# RPi-UNO-HAT_v10.net
KiCad netlist of a schematic drawn in EAGLE
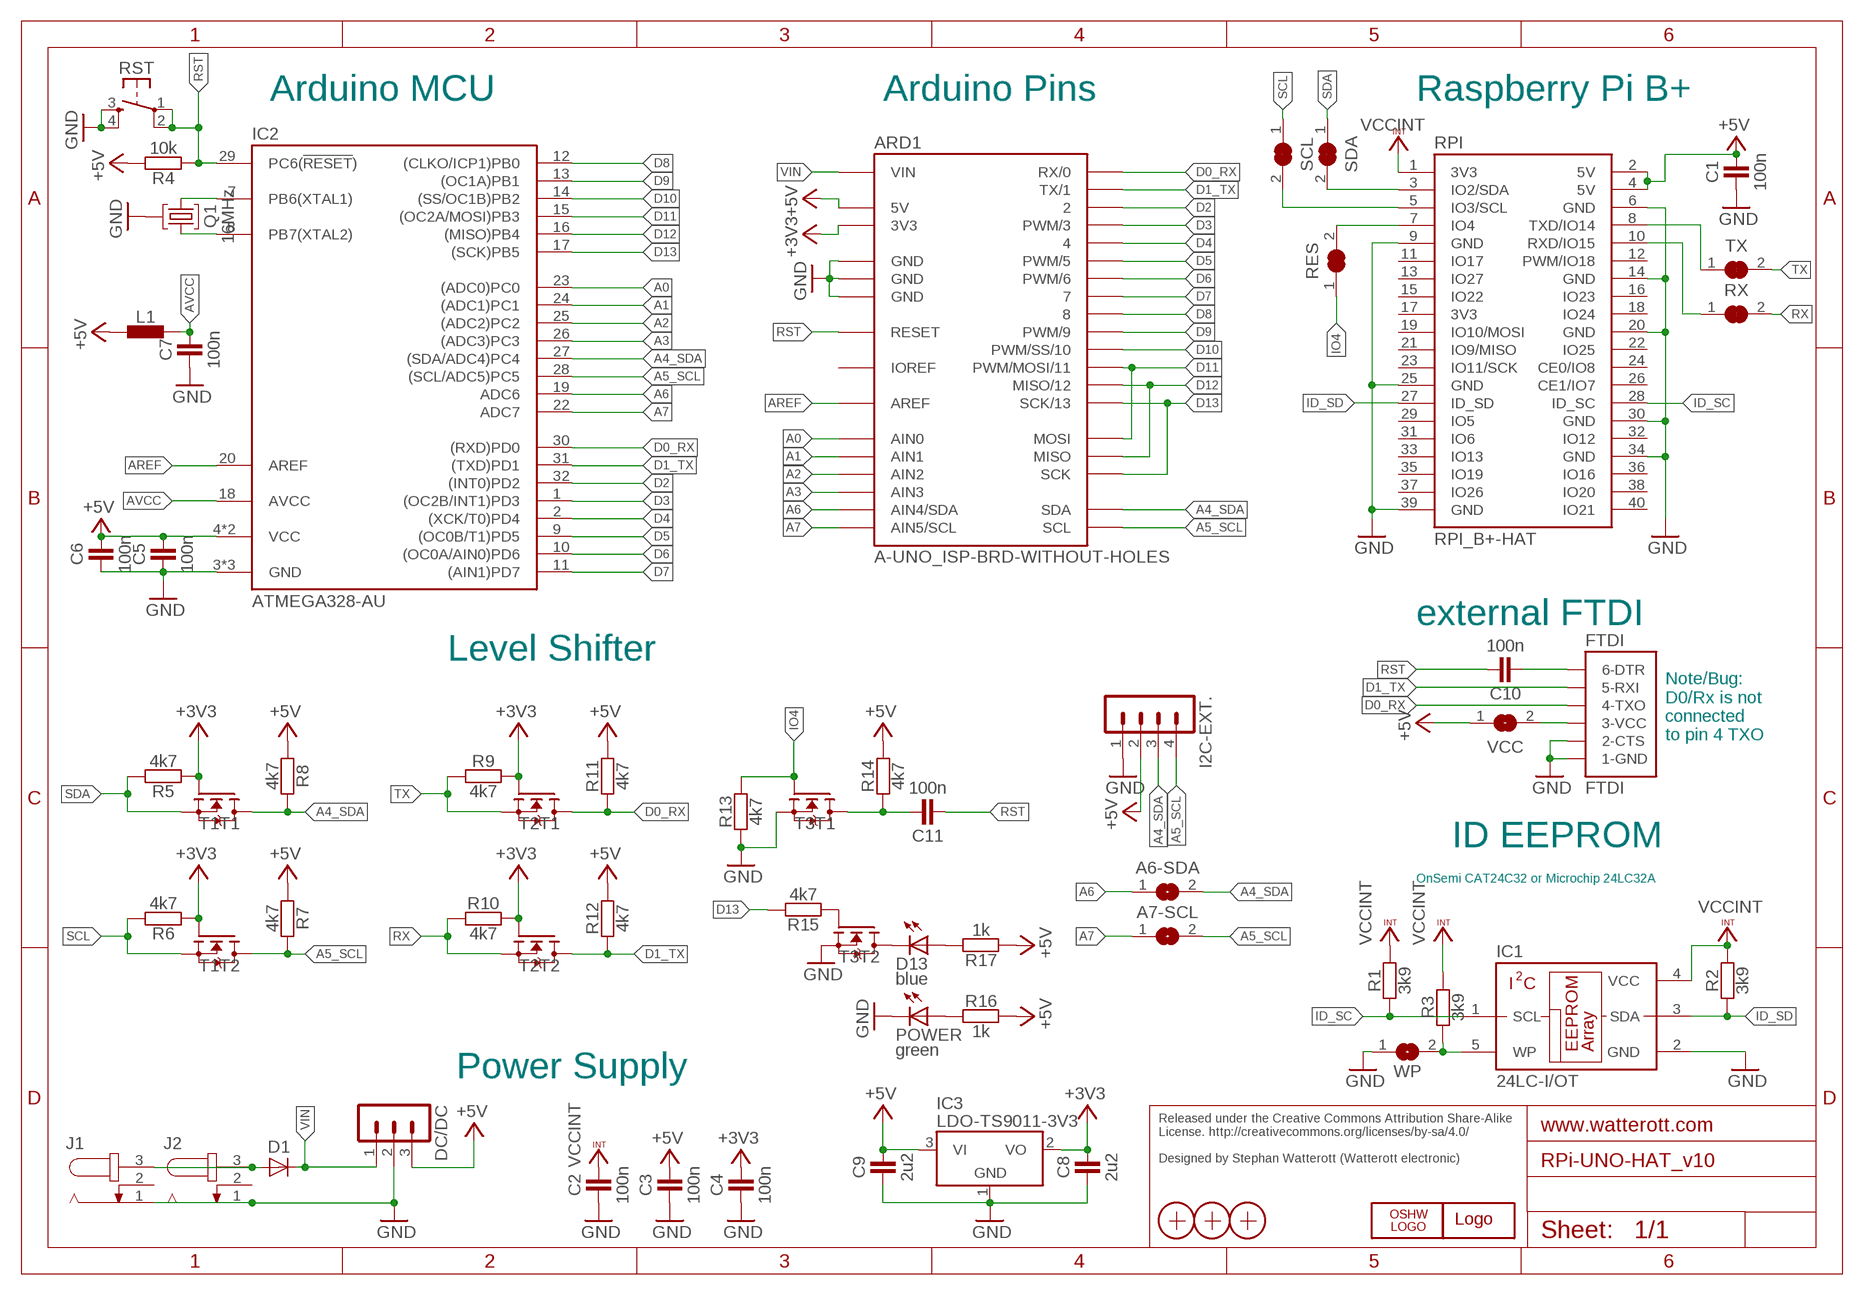
[diagram p0: schematic, sheet 1]

(export (version "E")
  (design (tool "Eeschema 10.0.6"))
  (components
    (comp (ref "A6-SDA")
      (value "JUMPER2-0402-NC")
      (footprint "eagle-import:JUMPER2-0402_NC")
      (libsource (lib "eagle-import") (part "JUMPER2-0402-NC"))
    )
    (comp (ref "A7-SCL")
      (value "JUMPER2-0402-NC")
      (footprint "eagle-import:JUMPER2-0402_NC")
      (libsource (lib "eagle-import") (part "JUMPER2-0402-NC"))
    )
    (comp (ref "ARD1")
      (value "A-UNO_ISP-BRD-WITHOUT-HOLES")
      (footprint "eagle-import:A-UNO-ISP_CON-WITHOUT-HOLES")
      (libsource (lib "eagle-import") (part "A-UNO_ISP-BRD-WITHOUT-HOLES"))
    )
    (comp (ref "C1")
      (value "100n")
      (footprint "eagle-import:C0402")
      (libsource (lib "eagle-import") (part "CAPACITOR-0402"))
    )
    (comp (ref "C2")
      (value "100n")
      (footprint "eagle-import:C0402")
      (libsource (lib "eagle-import") (part "CAPACITOR-0402"))
    )
    (comp (ref "C3")
      (value "100n")
      (footprint "eagle-import:C0402")
      (libsource (lib "eagle-import") (part "CAPACITOR-0402"))
    )
    (comp (ref "C4")
      (value "100n")
      (footprint "eagle-import:C0402")
      (libsource (lib "eagle-import") (part "CAPACITOR-0402"))
    )
    (comp (ref "C5")
      (value "100n")
      (footprint "eagle-import:C0402")
      (libsource (lib "eagle-import") (part "CAPACITOR-0402"))
    )
    (comp (ref "C6")
      (value "100n")
      (footprint "eagle-import:C0402")
      (libsource (lib "eagle-import") (part "CAPACITOR-0402"))
    )
    (comp (ref "C7")
      (value "100n")
      (footprint "eagle-import:C0402")
      (libsource (lib "eagle-import") (part "CAPACITOR-0402"))
    )
    (comp (ref "C8")
      (value "2u2")
      (footprint "eagle-import:C0402")
      (libsource (lib "eagle-import") (part "CAPACITOR-0402"))
    )
    (comp (ref "C9")
      (value "2u2")
      (footprint "eagle-import:C0402")
      (libsource (lib "eagle-import") (part "CAPACITOR-0402"))
    )
    (comp (ref "C10")
      (value "100n")
      (footprint "eagle-import:C0402")
      (libsource (lib "eagle-import") (part "CAPACITOR-0402"))
    )
    (comp (ref "C11")
      (value "100n")
      (footprint "eagle-import:C0402")
      (libsource (lib "eagle-import") (part "CAPACITOR-0402"))
    )
    (comp (ref "D1")
      (value "DIODE-SOD80")
      (footprint "eagle-import:SOD80")
      (libsource (lib "eagle-import") (part "DIODE-SOD80"))
    )
    (comp (ref "D13")
      (value "blue")
      (footprint "eagle-import:C0603")
      (libsource (lib "eagle-import") (part "LED-0603"))
    )
    (comp (ref "DC/DC")
      (value "MA03-1")
      (footprint "eagle-import:MA03-1")
      (libsource (lib "eagle-import") (part "MA03-1"))
    )
    (comp (ref "FTDI")
      (value "FTDI")
      (footprint "eagle-import:FTDI")
      (libsource (lib "eagle-import") (part "FTDI"))
    )
    (comp (ref "I2C-EXT.")
      (value "JST_PH_4B4B-PH-SM4-TB")
      (footprint "eagle-import:JST_B4B-PH-SM4-TB")
      (libsource (lib "eagle-import") (part "JST_PH_4B4B-PH-SM4-TB"))
    )
    (comp (ref "IC1")
      (value "24LC-I/OT")
      (footprint "eagle-import:SOT23-5")
      (libsource (lib "eagle-import") (part "24LC-I/OT"))
    )
    (comp (ref "IC2")
      (value "ATMEGA328-AU")
      (footprint "eagle-import:TQFP32")
      (libsource (lib "eagle-import") (part "ATMEGA328-AU"))
    )
    (comp (ref "IC3")
      (value "LDO-TS9011-3V3")
      (footprint "eagle-import:SOT23")
      (libsource (lib "eagle-import") (part "LDO-TS9011-3V3"))
    )
    (comp (ref "J1")
      (value "DC-JACK")
      (footprint "eagle-import:DC-JACK")
      (libsource (lib "eagle-import") (part "DC-JACK"))
    )
    (comp (ref "J2")
      (value "DC-JACK")
      (footprint "eagle-import:DC-JACK")
      (libsource (lib "eagle-import") (part "DC-JACK"))
    )
    (comp (ref "L1")
      (value "INDUCTOR-0603")
      (footprint "eagle-import:C0603")
      (libsource (lib "eagle-import") (part "INDUCTOR-0603"))
    )
    (comp (ref "LOGO1")
      (value "LOGO-S_PLACE_S")
      (footprint "eagle-import:SPARK_TPLACE_S")
      (libsource (lib "eagle-import") (part "LOGO-S_PLACE_S"))
    )
    (comp (ref "LOGO2")
      (value "OSHW_LOGOX0070")
      (footprint "eagle-import:OSHW_6X70")
      (libsource (lib "eagle-import") (part "OSHW_LOGOX0070"))
    )
    (comp (ref "POWER")
      (value "green")
      (footprint "eagle-import:C0603")
      (libsource (lib "eagle-import") (part "LED-0603"))
    )
    (comp (ref "Q1")
      (value "16MHz")
      (footprint "eagle-import:CRYSTAL_32X13")
      (libsource (lib "eagle-import") (part "CRYSTAL-RES-32"))
    )
    (comp (ref "R1")
      (value "3k9")
      (footprint "eagle-import:C0402")
      (libsource (lib "eagle-import") (part "RESISTOR-0402"))
    )
    (comp (ref "R2")
      (value "3k9")
      (footprint "eagle-import:C0402")
      (libsource (lib "eagle-import") (part "RESISTOR-0402"))
    )
    (comp (ref "R3")
      (value "3k9")
      (footprint "eagle-import:C0402")
      (libsource (lib "eagle-import") (part "RESISTOR-0402"))
    )
    (comp (ref "R4")
      (value "10k")
      (footprint "eagle-import:C0402")
      (libsource (lib "eagle-import") (part "RESISTOR-0402"))
    )
    (comp (ref "R5")
      (value "4k7")
      (footprint "eagle-import:C0402")
      (libsource (lib "eagle-import") (part "RESISTOR-0402"))
    )
    (comp (ref "R6")
      (value "4k7")
      (footprint "eagle-import:C0402")
      (libsource (lib "eagle-import") (part "RESISTOR-0402"))
    )
    (comp (ref "R7")
      (value "4k7")
      (footprint "eagle-import:C0402")
      (libsource (lib "eagle-import") (part "RESISTOR-0402"))
    )
    (comp (ref "R8")
      (value "4k7")
      (footprint "eagle-import:C0402")
      (libsource (lib "eagle-import") (part "RESISTOR-0402"))
    )
    (comp (ref "R9")
      (value "4k7")
      (footprint "eagle-import:C0402")
      (libsource (lib "eagle-import") (part "RESISTOR-0402"))
    )
    (comp (ref "R10")
      (value "4k7")
      (footprint "eagle-import:C0402")
      (libsource (lib "eagle-import") (part "RESISTOR-0402"))
    )
    (comp (ref "R11")
      (value "4k7")
      (footprint "eagle-import:C0402")
      (libsource (lib "eagle-import") (part "RESISTOR-0402"))
    )
    (comp (ref "R12")
      (value "4k7")
      (footprint "eagle-import:C0402")
      (libsource (lib "eagle-import") (part "RESISTOR-0402"))
    )
    (comp (ref "R13")
      (value "4k7")
      (footprint "eagle-import:C0402")
      (libsource (lib "eagle-import") (part "RESISTOR-0402"))
    )
    (comp (ref "R14")
      (value "4k7")
      (footprint "eagle-import:C0402")
      (libsource (lib "eagle-import") (part "RESISTOR-0402"))
    )
    (comp (ref "R15")
      (value "4k7")
      (footprint "eagle-import:C0402")
      (libsource (lib "eagle-import") (part "RESISTOR-0402"))
    )
    (comp (ref "R16")
      (value "1k")
      (footprint "eagle-import:C0402")
      (libsource (lib "eagle-import") (part "RESISTOR-0402"))
    )
    (comp (ref "R17")
      (value "1k")
      (footprint "eagle-import:C0402")
      (libsource (lib "eagle-import") (part "RESISTOR-0402"))
    )
    (comp (ref "RES")
      (value "JUMPER2-0402-NC")
      (footprint "eagle-import:JUMPER2-0402_NC")
      (libsource (lib "eagle-import") (part "JUMPER2-0402-NC"))
    )
    (comp (ref "RPI")
      (value "RPI_B+-HAT")
      (footprint "eagle-import:RPI-B+HAT")
      (libsource (lib "eagle-import") (part "RPI_B+-HAT"))
    )
    (comp (ref "RST")
      (value "SW-TACTILE-PTS840P")
      (footprint "eagle-import:SW_PTS840P")
      (libsource (lib "eagle-import") (part "SW-TACTILE-PTS840P"))
    )
    (comp (ref "RX")
      (value "JUMPER2-0402-NC")
      (footprint "eagle-import:JUMPER2-0402_NC")
      (libsource (lib "eagle-import") (part "JUMPER2-0402-NC"))
    )
    (comp (ref "SCL")
      (value "JUMPER2-0402-NC")
      (footprint "eagle-import:JUMPER2-0402_NC")
      (libsource (lib "eagle-import") (part "JUMPER2-0402-NC"))
    )
    (comp (ref "SDA")
      (value "JUMPER2-0402-NC")
      (footprint "eagle-import:JUMPER2-0402_NC")
      (libsource (lib "eagle-import") (part "JUMPER2-0402-NC"))
    )
    (comp (ref "T1")
      (value "BSS138PS")
      (footprint "eagle-import:SOT363")
      (libsource (lib "eagle-import") (part "BSS138PS"))
    )
    (comp (ref "T2")
      (value "BSS138PS")
      (footprint "eagle-import:SOT363")
      (libsource (lib "eagle-import") (part "BSS138PS"))
    )
    (comp (ref "T3")
      (value "BSS138PS")
      (footprint "eagle-import:SOT363")
      (libsource (lib "eagle-import") (part "BSS138PS"))
    )
    (comp (ref "TX")
      (value "JUMPER2-0402-NC")
      (footprint "eagle-import:JUMPER2-0402_NC")
      (libsource (lib "eagle-import") (part "JUMPER2-0402-NC"))
    )
    (comp (ref "VCC")
      (value "JUMPER2-0402-NC")
      (footprint "eagle-import:JUMPER2-0402_NC")
      (libsource (lib "eagle-import") (part "JUMPER2-0402-NC"))
    )
    (comp (ref "WP")
      (value "JUMPER2-0603-NC")
      (footprint "eagle-import:JUMPER2-0603_NC")
      (libsource (lib "eagle-import") (part "JUMPER2-0603-NC"))
    )
    (comp (ref "X1")
      (value "PASSER-07")
      (footprint "eagle-import:PASSER_07MM")
      (libsource (lib "eagle-import") (part "PASSER-07"))
    )
    (comp (ref "X2")
      (value "PASSER-07")
      (footprint "eagle-import:PASSER_07MM")
      (libsource (lib "eagle-import") (part "PASSER-07"))
    )
    (comp (ref "X3")
      (value "PASSER-07")
      (footprint "eagle-import:PASSER_07MM")
      (libsource (lib "eagle-import") (part "PASSER-07"))
    )
  )
  (nets
    (net (code "1") (name "+3V3") (class "Default")
      (node (ref "ARD1") (pin "3V3") (pinfunction "3V3_3V3") (pintype "power_in"))
      (node (ref "C4") (pin "2") (pinfunction "2_2") (pintype "passive"))
      (node (ref "C8") (pin "2") (pinfunction "2_2") (pintype "passive"))
      (node (ref "IC3") (pin "2") (pinfunction "VO_2") (pintype "passive"))
      (node (ref "R10") (pin "2") (pinfunction "2_2") (pintype "passive"))
      (node (ref "R5") (pin "1") (pinfunction "1_1") (pintype "passive"))
      (node (ref "R6") (pin "1") (pinfunction "1_1") (pintype "passive"))
      (node (ref "R9") (pin "2") (pinfunction "2_2") (pintype "passive"))
      (node (ref "T1") (pin "2") (pinfunction "G_2") (pintype "passive"))
      (node (ref "T1") (pin "5") (pinfunction "G_5") (pintype "passive"))
      (node (ref "T2") (pin "2") (pinfunction "G_2") (pintype "passive"))
      (node (ref "T2") (pin "5") (pinfunction "G_5") (pintype "passive"))
    )
    (net (code "2") (name "+5V") (class "Default")
      (node (ref "ARD1") (pin "5V") (pinfunction "5V_5V") (pintype "power_in"))
      (node (ref "ARD1") (pin "VCC") (pinfunction "5V_VCC") (pintype "power_in"))
      (node (ref "C1") (pin "2") (pinfunction "2_2") (pintype "passive"))
      (node (ref "C3") (pin "2") (pinfunction "2_2") (pintype "passive"))
      (node (ref "C5") (pin "2") (pinfunction "2_2") (pintype "passive"))
      (node (ref "C6") (pin "2") (pinfunction "2_2") (pintype "passive"))
      (node (ref "C9") (pin "2") (pinfunction "2_2") (pintype "passive"))
      (node (ref "DC/DC") (pin "3") (pinfunction "3_3") (pintype "passive"))
      (node (ref "I2C-EXT.") (pin "2") (pinfunction "2_2") (pintype "passive"))
      (node (ref "IC2") (pin "4") (pinfunction "VCC_4") (pintype "power_in"))
      (node (ref "IC2") (pin "6") (pinfunction "VCC_6") (pintype "power_in"))
      (node (ref "IC3") (pin "3") (pinfunction "VI_3") (pintype "input"))
      (node (ref "L1") (pin "1") (pinfunction "1_1") (pintype "passive"))
      (node (ref "R11") (pin "2") (pinfunction "2_2") (pintype "passive"))
      (node (ref "R12") (pin "2") (pinfunction "2_2") (pintype "passive"))
      (node (ref "R14") (pin "2") (pinfunction "2_2") (pintype "passive"))
      (node (ref "R16") (pin "2") (pinfunction "2_2") (pintype "passive"))
      (node (ref "R17") (pin "1") (pinfunction "1_1") (pintype "passive"))
      (node (ref "R4") (pin "2") (pinfunction "2_2") (pintype "passive"))
      (node (ref "R7") (pin "1") (pinfunction "1_1") (pintype "passive"))
      (node (ref "R8") (pin "1") (pinfunction "1_1") (pintype "passive"))
      (node (ref "RPI") (pin "2") (pinfunction "5V_2") (pintype "passive"))
      (node (ref "RPI") (pin "4") (pinfunction "5V_4") (pintype "passive"))
      (node (ref "VCC") (pin "1") (pinfunction "1_1") (pintype "passive"))
    )
    (net (code "3") (name "/IOREF") (class "Default")
      (node (ref "ARD1") (pin "IOREF") (pinfunction "IOREF_IOREF") (pintype "power_in"))
    )
    (net (code "4") (name "A0") (class "Default")
      (node (ref "ARD1") (pin "A0") (pinfunction "AIN0_A0") (pintype "bidirectional"))
      (node (ref "IC2") (pin "23") (pinfunction "(ADC0)PC0_23") (pintype "bidirectional"))
    )
    (net (code "5") (name "A1") (class "Default")
      (node (ref "ARD1") (pin "A1") (pinfunction "AIN1_A1") (pintype "bidirectional"))
      (node (ref "IC2") (pin "24") (pinfunction "(ADC1)PC1_24") (pintype "bidirectional"))
    )
    (net (code "6") (name "A2") (class "Default")
      (node (ref "ARD1") (pin "A2") (pinfunction "AIN2_A2") (pintype "bidirectional"))
      (node (ref "IC2") (pin "25") (pinfunction "(ADC2)PC2_25") (pintype "bidirectional"))
    )
    (net (code "7") (name "A3") (class "Default")
      (node (ref "ARD1") (pin "A3") (pinfunction "AIN3_A3") (pintype "bidirectional"))
      (node (ref "IC2") (pin "26") (pinfunction "(ADC3)PC3_26") (pintype "bidirectional"))
    )
    (net (code "8") (name "A4_SDA") (class "Default")
      (node (ref "A6-SDA") (pin "2") (pinfunction "2_2") (pintype "passive"))
      (node (ref "ARD1") (pin "SDA") (pinfunction "SDA_SDA") (pintype "bidirectional"))
      (node (ref "I2C-EXT.") (pin "3") (pinfunction "3_3") (pintype "passive"))
      (node (ref "IC2") (pin "27") (pinfunction "(SDA/ADC4)PC4_27") (pintype "bidirectional"))
      (node (ref "R8") (pin "2") (pinfunction "2_2") (pintype "passive"))
      (node (ref "T1") (pin "6") (pinfunction "D_6") (pintype "passive"))
    )
    (net (code "9") (name "A5_SCL") (class "Default")
      (node (ref "A7-SCL") (pin "2") (pinfunction "2_2") (pintype "passive"))
      (node (ref "ARD1") (pin "SCL") (pinfunction "SCL_SCL") (pintype "bidirectional"))
      (node (ref "I2C-EXT.") (pin "4") (pinfunction "4_4") (pintype "passive"))
      (node (ref "IC2") (pin "28") (pinfunction "(SCL/ADC5)PC5_28") (pintype "bidirectional"))
      (node (ref "R7") (pin "2") (pinfunction "2_2") (pintype "passive"))
      (node (ref "T1") (pin "3") (pinfunction "D_3") (pintype "passive"))
    )
    (net (code "10") (name "A6") (class "Default")
      (node (ref "A6-SDA") (pin "1") (pinfunction "1_1") (pintype "passive"))
      (node (ref "ARD1") (pin "A4") (pinfunction "AIN4/SDA_A4") (pintype "bidirectional"))
      (node (ref "IC2") (pin "19") (pinfunction "ADC6_19") (pintype "bidirectional"))
    )
    (net (code "11") (name "A7") (class "Default")
      (node (ref "A7-SCL") (pin "1") (pinfunction "1_1") (pintype "passive"))
      (node (ref "ARD1") (pin "A5") (pinfunction "AIN5/SCL_A5") (pintype "bidirectional"))
      (node (ref "IC2") (pin "22") (pinfunction "ADC7_22") (pintype "bidirectional"))
    )
    (net (code "12") (name "AREF") (class "Default")
      (node (ref "ARD1") (pin "AREF") (pinfunction "AREF_AREF") (pintype "power_in"))
      (node (ref "IC2") (pin "20") (pinfunction "AREF_20") (pintype "passive"))
    )
    (net (code "13") (name "AVCC") (class "Default")
      (node (ref "C7") (pin "2") (pinfunction "2_2") (pintype "passive"))
      (node (ref "IC2") (pin "18") (pinfunction "AVCC_18") (pintype "power_in"))
      (node (ref "L1") (pin "2") (pinfunction "2_2") (pintype "passive"))
    )
    (net (code "14") (name "D0_RX") (class "Default")
      (node (ref "ARD1") (pin "0") (pinfunction "RX/0_0") (pintype "bidirectional"))
      (node (ref "FTDI") (pin "4-TX") (pinfunction "4-TXO_4-TX") (pintype "bidirectional"))
      (node (ref "IC2") (pin "30") (pinfunction "(RXD)PD0_30") (pintype "bidirectional"))
      (node (ref "R11") (pin "1") (pinfunction "1_1") (pintype "passive"))
      (node (ref "T2") (pin "6") (pinfunction "D_6") (pintype "passive"))
    )
    (net (code "15") (name "D1_TX") (class "Default")
      (node (ref "ARD1") (pin "1") (pinfunction "TX/1_1") (pintype "bidirectional"))
      (node (ref "FTDI") (pin "5-RX") (pinfunction "5-RXI_5-RX") (pintype "bidirectional"))
      (node (ref "IC2") (pin "31") (pinfunction "(TXD)PD1_31") (pintype "bidirectional"))
      (node (ref "R12") (pin "1") (pinfunction "1_1") (pintype "passive"))
      (node (ref "T2") (pin "3") (pinfunction "D_3") (pintype "passive"))
    )
    (net (code "16") (name "D2") (class "Default")
      (node (ref "ARD1") (pin "2") (pinfunction "2_2") (pintype "bidirectional"))
      (node (ref "IC2") (pin "32") (pinfunction "(INT0)PD2_32") (pintype "bidirectional"))
    )
    (net (code "17") (name "D3") (class "Default")
      (node (ref "ARD1") (pin "3") (pinfunction "PWM/3_3") (pintype "bidirectional"))
      (node (ref "IC2") (pin "1") (pinfunction "(OC2B/INT1)PD3_1") (pintype "bidirectional"))
    )
    (net (code "18") (name "D4") (class "Default")
      (node (ref "ARD1") (pin "4") (pinfunction "4_4") (pintype "bidirectional"))
      (node (ref "IC2") (pin "2") (pinfunction "(XCK/T0)PD4_2") (pintype "bidirectional"))
    )
    (net (code "19") (name "D5") (class "Default")
      (node (ref "ARD1") (pin "5") (pinfunction "PWM/5_5") (pintype "bidirectional"))
      (node (ref "IC2") (pin "9") (pinfunction "(OC0B/T1)PD5_9") (pintype "bidirectional"))
    )
    (net (code "20") (name "D6") (class "Default")
      (node (ref "ARD1") (pin "6") (pinfunction "PWM/6_6") (pintype "bidirectional"))
      (node (ref "IC2") (pin "10") (pinfunction "(OC0A/AIN0)PD6_10") (pintype "bidirectional"))
    )
    (net (code "21") (name "D7") (class "Default")
      (node (ref "ARD1") (pin "7") (pinfunction "7_7") (pintype "bidirectional"))
      (node (ref "IC2") (pin "11") (pinfunction "(AIN1)PD7_11") (pintype "bidirectional"))
    )
    (net (code "22") (name "D8") (class "Default")
      (node (ref "ARD1") (pin "8") (pinfunction "8_8") (pintype "bidirectional"))
      (node (ref "IC2") (pin "12") (pinfunction "(CLKO/ICP1)PB0_12") (pintype "bidirectional"))
    )
    (net (code "23") (name "D9") (class "Default")
      (node (ref "ARD1") (pin "9") (pinfunction "PWM/9_9") (pintype "bidirectional"))
      (node (ref "IC2") (pin "13") (pinfunction "(OC1A)PB1_13") (pintype "bidirectional"))
    )
    (net (code "24") (name "D10") (class "Default")
      (node (ref "ARD1") (pin "10") (pinfunction "PWM/SS/10_10") (pintype "bidirectional"))
      (node (ref "IC2") (pin "14") (pinfunction "(SS/OC1B)PB2_14") (pintype "bidirectional"))
    )
    (net (code "25") (name "D11") (class "Default")
      (node (ref "ARD1") (pin "11") (pinfunction "PWM/MOSI/11_11") (pintype "bidirectional"))
      (node (ref "ARD1") (pin "MOSI") (pinfunction "MOSI_MOSI") (pintype "bidirectional"))
      (node (ref "IC2") (pin "15") (pinfunction "(OC2A/MOSI)PB3_15") (pintype "bidirectional"))
    )
    (net (code "26") (name "D12") (class "Default")
      (node (ref "ARD1") (pin "12") (pinfunction "MISO/12_12") (pintype "bidirectional"))
      (node (ref "ARD1") (pin "MISO") (pinfunction "MISO_MISO") (pintype "bidirectional"))
      (node (ref "IC2") (pin "16") (pinfunction "(MISO)PB4_16") (pintype "bidirectional"))
    )
    (net (code "27") (name "D13") (class "Default")
      (node (ref "ARD1") (pin "13") (pinfunction "SCK/13_13") (pintype "bidirectional"))
      (node (ref "ARD1") (pin "SCK") (pinfunction "SCK_SCK") (pintype "bidirectional"))
      (node (ref "IC2") (pin "17") (pinfunction "(SCK)PB5_17") (pintype "bidirectional"))
      (node (ref "R15") (pin "2") (pinfunction "2_2") (pintype "passive"))
    )
    (net (code "28") (name "GND") (class "Default")
      (node (ref "ARD1") (pin "GND@1") (pinfunction "GND_GND@1") (pintype "power_in"))
      (node (ref "ARD1") (pin "GND@2") (pinfunction "GND_GND@2") (pintype "power_in"))
      (node (ref "ARD1") (pin "GND@3") (pinfunction "GND_GND@3") (pintype "power_in"))
      (node (ref "ARD1") (pin "GND@4") (pinfunction "GND_GND@4") (pintype "power_in"))
      (node (ref "C1") (pin "1") (pinfunction "1_1") (pintype "passive"))
      (node (ref "C2") (pin "1") (pinfunction "1_1") (pintype "passive"))
      (node (ref "C3") (pin "1") (pinfunction "1_1") (pintype "passive"))
      (node (ref "C4") (pin "1") (pinfunction "1_1") (pintype "passive"))
      (node (ref "C5") (pin "1") (pinfunction "1_1") (pintype "passive"))
      (node (ref "C6") (pin "1") (pinfunction "1_1") (pintype "passive"))
      (node (ref "C7") (pin "1") (pinfunction "1_1") (pintype "passive"))
      (node (ref "C8") (pin "1") (pinfunction "1_1") (pintype "passive"))
      (node (ref "C9") (pin "1") (pinfunction "1_1") (pintype "passive"))
      (node (ref "DC/DC") (pin "2") (pinfunction "2_2") (pintype "passive"))
      (node (ref "FTDI") (pin "1-GND") (pinfunction "1-GND_1-GND") (pintype "power_in"))
      (node (ref "FTDI") (pin "2-CTS") (pinfunction "2-CTS_2-CTS") (pintype "bidirectional"))
      (node (ref "I2C-EXT.") (pin "1") (pinfunction "1_1") (pintype "passive"))
      (node (ref "IC1") (pin "2") (pinfunction "GND_2") (pintype "power_in"))
      (node (ref "IC2") (pin "21") (pinfunction "GND_21") (pintype "power_in"))
      (node (ref "IC2") (pin "3") (pinfunction "GND_3") (pintype "power_in"))
      (node (ref "IC2") (pin "5") (pinfunction "GND_5") (pintype "power_in"))
      (node (ref "IC3") (pin "1") (pinfunction "GND_1") (pintype "passive"))
      (node (ref "J1") (pin "1") (pinfunction "1_1") (pintype "passive"))
      (node (ref "J2") (pin "1") (pinfunction "1_1") (pintype "passive"))
      (node (ref "POWER") (pin "C") (pinfunction "C_C") (pintype "passive"))
      (node (ref "Q1") (pin "GND") (pinfunction "GND_GND") (pintype "passive"))
      (node (ref "R13") (pin "1") (pinfunction "1_1") (pintype "passive"))
      (node (ref "RPI") (pin "14") (pinfunction "GND_14") (pintype "passive"))
      (node (ref "RPI") (pin "20") (pinfunction "GND_20") (pintype "passive"))
      (node (ref "RPI") (pin "25") (pinfunction "GND_25") (pintype "passive"))
      (node (ref "RPI") (pin "30") (pinfunction "GND_30") (pintype "bidirectional"))
      (node (ref "RPI") (pin "34") (pinfunction "GND_34") (pintype "bidirectional"))
      (node (ref "RPI") (pin "39") (pinfunction "GND_39") (pintype "bidirectional"))
      (node (ref "RPI") (pin "6") (pinfunction "GND_6") (pintype "passive"))
      (node (ref "RPI") (pin "9") (pinfunction "GND_9") (pintype "passive"))
      (node (ref "RST") (pin "3") (pinfunction "S1_3") (pintype "passive"))
      (node (ref "RST") (pin "4") (pinfunction "S2_4") (pintype "passive"))
      (node (ref "T3") (pin "1") (pinfunction "S_1") (pintype "passive"))
      (node (ref "T3") (pin "4") (pinfunction "S_4") (pintype "passive"))
      (node (ref "WP") (pin "1") (pinfunction "1_1") (pintype "passive"))
    )
    (net (code "29") (name "ID_SC") (class "Default")
      (node (ref "IC1") (pin "1") (pinfunction "SCL_1") (pintype "bidirectional"))
      (node (ref "R1") (pin "1") (pinfunction "1_1") (pintype "passive"))
      (node (ref "RPI") (pin "28") (pinfunction "ID_SC_28") (pintype "bidirectional"))
    )
    (net (code "30") (name "ID_SD") (class "Default")
      (node (ref "IC1") (pin "3") (pinfunction "SDA_3") (pintype "bidirectional"))
      (node (ref "R2") (pin "1") (pinfunction "1_1") (pintype "passive"))
      (node (ref "RPI") (pin "27") (pinfunction "ID_SD_27") (pintype "bidirectional"))
    )
    (net (code "31") (name "IO4") (class "Default")
      (node (ref "R13") (pin "2") (pinfunction "2_2") (pintype "passive"))
      (node (ref "RES") (pin "1") (pinfunction "1_1") (pintype "passive"))
      (node (ref "T3") (pin "2") (pinfunction "G_2") (pintype "passive"))
    )
    (net (code "32") (name "Net-(C10-Pad1)") (class "Default")
      (node (ref "C10") (pin "1") (pinfunction "1_1") (pintype "passive"))
      (node (ref "FTDI") (pin "6-DTR") (pinfunction "6-DTR_6-DTR") (pintype "bidirectional"))
    )
    (net (code "33") (name "Net-(D1-PadA)") (class "Default")
      (node (ref "D1") (pin "A") (pinfunction "A_A") (pintype "passive"))
      (node (ref "J1") (pin "3") (pinfunction "3_3") (pintype "passive"))
      (node (ref "J2") (pin "3") (pinfunction "3_3") (pintype "passive"))
    )
    (net (code "34") (name "Net-(D13-PadA)") (class "Default")
      (node (ref "D13") (pin "A") (pinfunction "A_A") (pintype "passive"))
      (node (ref "R17") (pin "2") (pinfunction "2_2") (pintype "passive"))
    )
    (net (code "35") (name "Net-(FTDI-Pad3-VCC)") (class "Default")
      (node (ref "FTDI") (pin "3-VCC") (pinfunction "3-VCC_3-VCC") (pintype "power_in"))
      (node (ref "VCC") (pin "2") (pinfunction "2_2") (pintype "passive"))
    )
    (net (code "36") (name "Net-(IC1-WP)") (class "Default")
      (node (ref "IC1") (pin "5") (pinfunction "WP_5") (pintype "bidirectional"))
      (node (ref "R3") (pin "1") (pinfunction "1_1") (pintype "passive"))
      (node (ref "WP") (pin "2") (pinfunction "2_2") (pintype "passive"))
    )
    (net (code "37") (name "Net-(IC2-PB6(XTAL1))") (class "Default")
      (node (ref "IC2") (pin "7") (pinfunction "PB6(XTAL1)_7") (pintype "bidirectional"))
      (node (ref "Q1") (pin "2") (pinfunction "2_2") (pintype "passive"))
    )
    (net (code "38") (name "Net-(IC2-PB7(XTAL2))") (class "Default")
      (node (ref "IC2") (pin "8") (pinfunction "PB7(XTAL2)_8") (pintype "bidirectional"))
      (node (ref "Q1") (pin "1") (pinfunction "1_1") (pintype "passive"))
    )
    (net (code "39") (name "Net-(POWER-PadA)") (class "Default")
      (node (ref "POWER") (pin "A") (pinfunction "A_A") (pintype "passive"))
      (node (ref "R16") (pin "1") (pinfunction "1_1") (pintype "passive"))
    )
    (net (code "40") (name "Net-(RPI-IO2{slash}SDA)") (class "Default")
      (node (ref "RPI") (pin "3") (pinfunction "IO2/SDA_3") (pintype "passive"))
      (node (ref "SDA") (pin "2") (pinfunction "2_2") (pintype "passive"))
    )
    (net (code "41") (name "Net-(RPI-IO3{slash}SCL)") (class "Default")
      (node (ref "RPI") (pin "5") (pinfunction "IO3/SCL_5") (pintype "passive"))
      (node (ref "SCL") (pin "2") (pinfunction "2_2") (pintype "passive"))
    )
    (net (code "42") (name "Net-(RPI-IO4)") (class "Default")
      (node (ref "RES") (pin "2") (pinfunction "2_2") (pintype "passive"))
      (node (ref "RPI") (pin "7") (pinfunction "IO4_7") (pintype "passive"))
    )
    (net (code "43") (name "Net-(RPI-RXD{slash}IO15)") (class "Default")
      (node (ref "RPI") (pin "10") (pinfunction "RXD/IO15_10") (pintype "passive"))
      (node (ref "RX") (pin "1") (pinfunction "1_1") (pintype "passive"))
    )
    (net (code "44") (name "Net-(RPI-TXD{slash}IO14)") (class "Default")
      (node (ref "RPI") (pin "8") (pinfunction "TXD/IO14_8") (pintype "passive"))
      (node (ref "TX") (pin "1") (pinfunction "1_1") (pintype "passive"))
    )
    (net (code "45") (name "Net-(T3A-D)") (class "Default")
      (node (ref "C11") (pin "2") (pinfunction "2_2") (pintype "passive"))
      (node (ref "R14") (pin "1") (pinfunction "1_1") (pintype "passive"))
      (node (ref "T3") (pin "6") (pinfunction "D_6") (pintype "passive"))
    )
    (net (code "46") (name "Net-(T3B-D)") (class "Default")
      (node (ref "D13") (pin "C") (pinfunction "C_C") (pintype "passive"))
      (node (ref "T3") (pin "3") (pinfunction "D_3") (pintype "passive"))
    )
    (net (code "47") (name "Net-(T3B-G)") (class "Default")
      (node (ref "R15") (pin "1") (pinfunction "1_1") (pintype "passive"))
      (node (ref "T3") (pin "5") (pinfunction "G_5") (pintype "passive"))
    )
    (net (code "48") (name "RST") (class "Default")
      (node (ref "ARD1") (pin "RST") (pinfunction "RESET_RST") (pintype "bidirectional"))
      (node (ref "ARD1") (pin "RST2") (pinfunction "RESET_RST2") (pintype "bidirectional"))
      (node (ref "C10") (pin "2") (pinfunction "2_2") (pintype "passive"))
      (node (ref "C11") (pin "1") (pinfunction "1_1") (pintype "passive"))
      (node (ref "IC2") (pin "29") (pinfunction "PC6(~{RESET})_29") (pintype "bidirectional"))
      (node (ref "R4") (pin "1") (pinfunction "1_1") (pintype "passive"))
      (node (ref "RST") (pin "1") (pinfunction "P1_1") (pintype "passive"))
      (node (ref "RST") (pin "2") (pinfunction "P2_2") (pintype "passive"))
    )
    (net (code "49") (name "RX") (class "Default")
      (node (ref "R10") (pin "1") (pinfunction "1_1") (pintype "passive"))
      (node (ref "RX") (pin "2") (pinfunction "2_2") (pintype "passive"))
      (node (ref "T2") (pin "4") (pinfunction "S_4") (pintype "passive"))
    )
    (net (code "50") (name "SCL") (class "Default")
      (node (ref "R6") (pin "2") (pinfunction "2_2") (pintype "passive"))
      (node (ref "SCL") (pin "1") (pinfunction "1_1") (pintype "passive"))
      (node (ref "T1") (pin "4") (pinfunction "S_4") (pintype "passive"))
    )
    (net (code "51") (name "SDA") (class "Default")
      (node (ref "R5") (pin "2") (pinfunction "2_2") (pintype "passive"))
      (node (ref "SDA") (pin "1") (pinfunction "1_1") (pintype "passive"))
      (node (ref "T1") (pin "1") (pinfunction "S_1") (pintype "passive"))
    )
    (net (code "52") (name "TX") (class "Default")
      (node (ref "R9") (pin "1") (pinfunction "1_1") (pintype "passive"))
      (node (ref "T2") (pin "1") (pinfunction "S_1") (pintype "passive"))
      (node (ref "TX") (pin "2") (pinfunction "2_2") (pintype "passive"))
    )
    (net (code "53") (name "VCCINT") (class "Default")
      (node (ref "C2") (pin "2") (pinfunction "2_2") (pintype "passive"))
      (node (ref "IC1") (pin "4") (pinfunction "VCC_4") (pintype "power_in"))
      (node (ref "R1") (pin "2") (pinfunction "2_2") (pintype "passive"))
      (node (ref "R2") (pin "2") (pinfunction "2_2") (pintype "passive"))
      (node (ref "R3") (pin "2") (pinfunction "2_2") (pintype "passive"))
      (node (ref "RPI") (pin "1") (pinfunction "3V3_1") (pintype "passive"))
    )
    (net (code "54") (name "VIN") (class "Default")
      (node (ref "ARD1") (pin "VIN") (pinfunction "VIN_VIN") (pintype "power_in"))
      (node (ref "D1") (pin "C") (pinfunction "C_C") (pintype "passive"))
      (node (ref "DC/DC") (pin "1") (pinfunction "1_1") (pintype "passive"))
    )
    (net (code "55") (name "unconnected-(J1-Pad2)") (class "Default")
      (node (ref "J1") (pin "2") (pinfunction "2_2") (pintype "passive"))
    )
    (net (code "56") (name "unconnected-(J2-Pad2)") (class "Default")
      (node (ref "J2") (pin "2") (pinfunction "2_2") (pintype "passive"))
    )
    (net (code "57") (name "unconnected-(RPI-3V3-Pad17)") (class "Default")
      (node (ref "RPI") (pin "17") (pinfunction "3V3_17") (pintype "passive"))
    )
    (net (code "58") (name "unconnected-(RPI-CE0{slash}IO8-Pad24)") (class "Default")
      (node (ref "RPI") (pin "24") (pinfunction "CE0/IO8_24") (pintype "passive"))
    )
    (net (code "59") (name "unconnected-(RPI-CE1{slash}IO7-Pad26)") (class "Default")
      (node (ref "RPI") (pin "26") (pinfunction "CE1/IO7_26") (pintype "passive"))
    )
    (net (code "60") (name "unconnected-(RPI-IO5-Pad29)") (class "Default")
      (node (ref "RPI") (pin "29") (pinfunction "IO5_29") (pintype "bidirectional"))
    )
    (net (code "61") (name "unconnected-(RPI-IO6-Pad31)") (class "Default")
      (node (ref "RPI") (pin "31") (pinfunction "IO6_31") (pintype "bidirectional"))
    )
    (net (code "62") (name "unconnected-(RPI-IO9{slash}MISO-Pad21)") (class "Default")
      (node (ref "RPI") (pin "21") (pinfunction "IO9/MISO_21") (pintype "passive"))
    )
    (net (code "63") (name "unconnected-(RPI-IO10{slash}MOSI-Pad19)") (class "Default")
      (node (ref "RPI") (pin "19") (pinfunction "IO10/MOSI_19") (pintype "passive"))
    )
    (net (code "64") (name "unconnected-(RPI-IO11{slash}SCK-Pad23)") (class "Default")
      (node (ref "RPI") (pin "23") (pinfunction "IO11/SCK_23") (pintype "passive"))
    )
    (net (code "65") (name "unconnected-(RPI-IO12-Pad32)") (class "Default")
      (node (ref "RPI") (pin "32") (pinfunction "IO12_32") (pintype "bidirectional"))
    )
    (net (code "66") (name "unconnected-(RPI-IO13-Pad33)") (class "Default")
      (node (ref "RPI") (pin "33") (pinfunction "IO13_33") (pintype "bidirectional"))
    )
    (net (code "67") (name "unconnected-(RPI-IO16-Pad36)") (class "Default")
      (node (ref "RPI") (pin "36") (pinfunction "IO16_36") (pintype "bidirectional"))
    )
    (net (code "68") (name "unconnected-(RPI-IO17-Pad11)") (class "Default")
      (node (ref "RPI") (pin "11") (pinfunction "IO17_11") (pintype "passive"))
    )
    (net (code "69") (name "unconnected-(RPI-IO19-Pad35)") (class "Default")
      (node (ref "RPI") (pin "35") (pinfunction "IO19_35") (pintype "bidirectional"))
    )
    (net (code "70") (name "unconnected-(RPI-IO20-Pad38)") (class "Default")
      (node (ref "RPI") (pin "38") (pinfunction "IO20_38") (pintype "bidirectional"))
    )
    (net (code "71") (name "unconnected-(RPI-IO21-Pad40)") (class "Default")
      (node (ref "RPI") (pin "40") (pinfunction "IO21_40") (pintype "bidirectional"))
    )
    (net (code "72") (name "unconnected-(RPI-IO22-Pad15)") (class "Default")
      (node (ref "RPI") (pin "15") (pinfunction "IO22_15") (pintype "passive"))
    )
    (net (code "73") (name "unconnected-(RPI-IO23-Pad16)") (class "Default")
      (node (ref "RPI") (pin "16") (pinfunction "IO23_16") (pintype "passive"))
    )
    (net (code "74") (name "unconnected-(RPI-IO24-Pad18)") (class "Default")
      (node (ref "RPI") (pin "18") (pinfunction "IO24_18") (pintype "passive"))
    )
    (net (code "75") (name "unconnected-(RPI-IO25-Pad22)") (class "Default")
      (node (ref "RPI") (pin "22") (pinfunction "IO25_22") (pintype "passive"))
    )
    (net (code "76") (name "unconnected-(RPI-IO26-Pad37)") (class "Default")
      (node (ref "RPI") (pin "37") (pinfunction "IO26_37") (pintype "bidirectional"))
    )
    (net (code "77") (name "unconnected-(RPI-IO27-Pad13)") (class "Default")
      (node (ref "RPI") (pin "13") (pinfunction "IO27_13") (pintype "passive"))
    )
    (net (code "78") (name "unconnected-(RPI-PWM{slash}IO18-Pad12)") (class "Default")
      (node (ref "RPI") (pin "12") (pinfunction "PWM/IO18_12") (pintype "passive"))
    )
  )
)
